# cm108_schematic_2022-07-07.net
KiCad netlist of a schematic drawn in Altium Designer
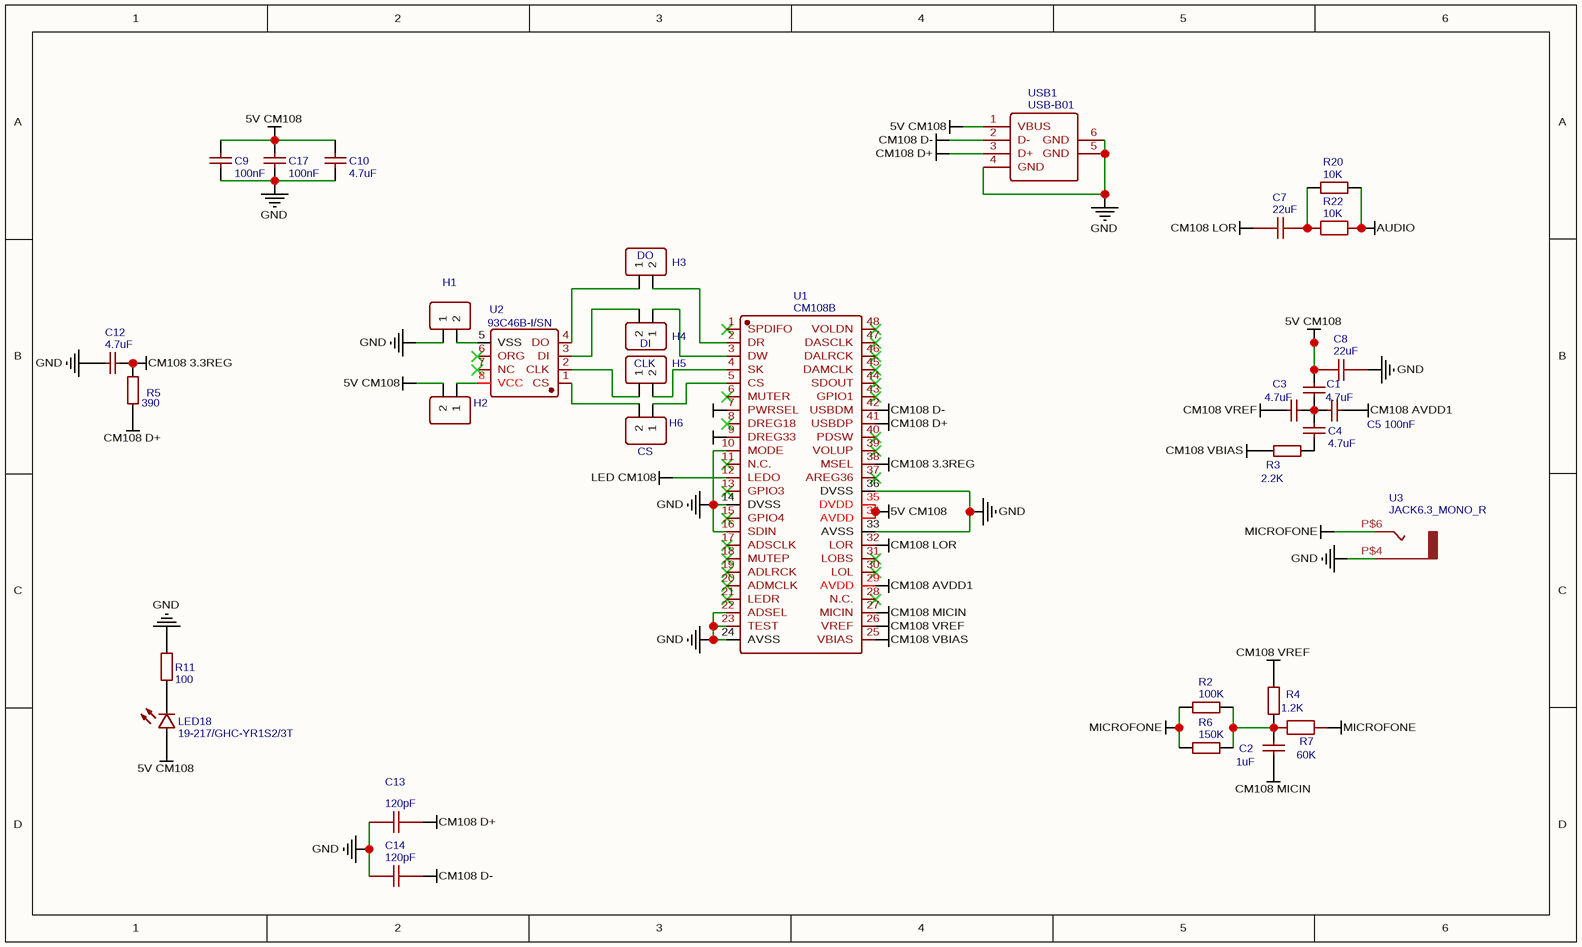
[diagram p0: cm108 schematic_2022-07-07.schdoc]

(export (version "E")
  (design (tool "Eeschema 10.0.6"))
  (components
    (comp (ref "C1")
      (value "4.7uF")
      (fields
        (field (name "BOM_MANUFACTURER PART") "CL21A475KAQNNNE")
        (field (name "BOM_SUPPLIER PART") "C1779")
      )
      (libsource (lib "altium-import") (part "root_3_4.7uF_"))
    )
    (comp (ref "C2")
      (value "1uF")
      (fields
        (field (name "BOM_MANUFACTURER PART") "CL21B105KBFNNNE")
        (field (name "BOM_SUPPLIER PART") "C28323")
      )
      (libsource (lib "altium-import") (part "root_1_1uF_"))
    )
    (comp (ref "C3")
      (value "4.7uF")
      (fields
        (field (name "BOM_MANUFACTURER PART") "CL21A475KAQNNNE")
        (field (name "BOM_SUPPLIER PART") "C1779")
      )
      (libsource (lib "altium-import") (part "root_2_4.7uF_"))
    )
    (comp (ref "C4")
      (value "4.7uF")
      (fields
        (field (name "BOM_MANUFACTURER PART") "CL21A475KAQNNNE")
        (field (name "BOM_SUPPLIER PART") "C1779")
      )
      (libsource (lib "altium-import") (part "root_3_4.7uF_"))
    )
    (comp (ref "C5")
      (value "100nF")
      (fields
        (field (name "BOM_MANUFACTURER PART") "CC0805KRX7R9BB104")
        (field (name "BOM_SUPPLIER PART") "C49678")
      )
      (libsource (lib "altium-import") (part "root_0_100nF_"))
    )
    (comp (ref "C7")
      (value "22uF")
      (fields
        (field (name "BOM_MANUFACTURER PART") "CL21A226MAQNNNE")
        (field (name "BOM_SUPPLIER PART") "C45783")
      )
      (libsource (lib "altium-import") (part "root_0_22uF_"))
    )
    (comp (ref "C8")
      (value "22uF")
      (fields
        (field (name "BOM_MANUFACTURER PART") "CL21A226MAQNNNE")
        (field (name "BOM_SUPPLIER PART") "C45783")
      )
      (libsource (lib "altium-import") (part "root_0_22uF_"))
    )
    (comp (ref "C9")
      (value "100nF")
      (fields
        (field (name "BOM_MANUFACTURER PART") "CC0805KRX7R9BB104")
        (field (name "BOM_SUPPLIER PART") "C49678")
      )
      (libsource (lib "altium-import") (part "root_1_100nF_"))
    )
    (comp (ref "C10")
      (value "4.7uF")
      (fields
        (field (name "BOM_MANUFACTURER PART") "CL21A475KAQNNNE")
        (field (name "BOM_SUPPLIER PART") "C1779")
      )
      (libsource (lib "altium-import") (part "root_1_4.7uF_"))
    )
    (comp (ref "C12")
      (value "4.7uF")
      (fields
        (field (name "BOM_MANUFACTURER PART") "CL21A475KAQNNNE")
        (field (name "BOM_SUPPLIER PART") "C1779")
      )
      (libsource (lib "altium-import") (part "root_0_4.7uF_"))
    )
    (comp (ref "C13")
      (value "120pF")
      (fields
        (field (name "BOM_SUPPLIER PART") "C159770")
        (field (name "BOM_MANUFACTURER PART") "CL21C121JBANNNC")
        (field (name "CONTRIBUTOR") "LCSC")
      )
      (libsource (lib "altium-import") (part "root_1_120pF_"))
    )
    (comp (ref "C14")
      (value "120pF")
      (fields
        (field (name "BOM_SUPPLIER PART") "C159770")
        (field (name "BOM_MANUFACTURER PART") "CL21C121JBANNNC")
        (field (name "CONTRIBUTOR") "LCSC")
      )
      (libsource (lib "altium-import") (part "root_1_120pF_"))
    )
    (comp (ref "C17")
      (value "100nF")
      (fields
        (field (name "BOM_MANUFACTURER PART") "CC0805KRX7R9BB104")
        (field (name "BOM_SUPPLIER PART") "C49678")
      )
      (libsource (lib "altium-import") (part "root_1_100nF_"))
    )
    (comp (ref "H1")
      (value "HDR-F-2.54_1x2")
      (fields (field (name "BOM_SUPPLIER PART") "C49661") (field (name "CONTRIBUTOR") "LCEDA_Lib"))
      (libsource (lib "altium-import") (part "root_1_HDR-F-2.54_1x2_"))
    )
    (comp (ref "H2")
      (value "HDR-F-2.54_1x2")
      (fields (field (name "BOM_SUPPLIER PART") "C49661") (field (name "CONTRIBUTOR") "LCEDA_Lib"))
      (libsource (lib "altium-import") (part "root_3_HDR-F-2.54_1x2_"))
    )
    (comp (ref "H3")
      (value "DO")
      (fields (field (name "BOM_SUPPLIER PART") "C49661") (field (name "CONTRIBUTOR") "LCEDA_Lib"))
      (libsource (lib "altium-import") (part "root_1_DO_"))
    )
    (comp (ref "H4")
      (value "DI")
      (fields (field (name "BOM_SUPPLIER PART") "C49661") (field (name "CONTRIBUTOR") "LCEDA_Lib"))
      (libsource (lib "altium-import") (part "root_3_DI_"))
    )
    (comp (ref "H5")
      (value "CLK")
      (fields (field (name "BOM_SUPPLIER PART") "C49661") (field (name "CONTRIBUTOR") "LCEDA_Lib"))
      (libsource (lib "altium-import") (part "root_1_CLK_"))
    )
    (comp (ref "H6")
      (value "CS")
      (fields (field (name "BOM_SUPPLIER PART") "C49661") (field (name "CONTRIBUTOR") "LCEDA_Lib"))
      (libsource (lib "altium-import") (part "root_3_CS_"))
    )
    (comp (ref "LED18")
      (value "19-217/GHC-YR1S2/3T")
      (fields (field (name "BOM_SUPPLIER PART") "C72043"))
      (libsource (lib "altium-import") (part "root_1_19-217/GHC-YR1S2/3T_"))
    )
    (comp (ref "R2")
      (value "100K")
      (fields
        (field (name "BOM_MANUFACTURER PART") "0603WAF1003T5E")
        (field (name "BOM_SUPPLIER PART") "C25803")
      )
      (libsource (lib "altium-import") (part "root_2_100K_"))
    )
    (comp (ref "R3")
      (value "2.2K")
      (fields
        (field (name "BOM_MANUFACTURER PART") "0805W8F2201T5E")
        (field (name "BOM_SUPPLIER PART") "C17520")
      )
      (libsource (lib "altium-import") (part "root_2_2.2K_"))
    )
    (comp (ref "R4")
      (value "1.2K")
      (fields
        (field (name "BOM_MANUFACTURER PART") "0805W8F1201T5E")
        (field (name "BOM_SUPPLIER PART") "C17379")
      )
      (libsource (lib "altium-import") (part "root_1_1.2K_"))
    )
    (comp (ref "R5")
      (value "390")
      (fields
        (field (name "BOM_MANUFACTURER PART") "1206W4J0391T5E")
        (field (name "BOM_SUPPLIER PART") "C25378")
      )
      (libsource (lib "altium-import") (part "root_1_390_"))
    )
    (comp (ref "R6")
      (value "150K")
      (fields
        (field (name "BOM_MANUFACTURER PART") "0603WAF1503T5E")
        (field (name "BOM_SUPPLIER PART") "C22807")
      )
      (libsource (lib "altium-import") (part "root_2_150K_"))
    )
    (comp (ref "R7")
      (value "60K")
      (fields
        (field (name "BOM_SUPPLIER PART") "C410695")
        (field (name "BOM_MANUFACTURER PART") "RN 1/4W 10K F T/B A1")
        (field (name "CONTRIBUTOR") "LCSC")
      )
      (libsource (lib "altium-import") (part "root_0_60K_"))
    )
    (comp (ref "R11")
      (value "100")
      (fields
        (field (name "BOM_MANUFACTURER PART") "0805W8F1000T5E")
        (field (name "BOM_SUPPLIER PART") "C17408")
      )
      (libsource (lib "altium-import") (part "root_1_100_"))
    )
    (comp (ref "R20")
      (value "10K")
      (fields
        (field (name "BOM_MANUFACTURER PART") "0603WAF1002T5E")
        (field (name "BOM_SUPPLIER PART") "C25804")
      )
      (libsource (lib "altium-import") (part "root_2_10K_"))
    )
    (comp (ref "R22")
      (value "10K")
      (fields
        (field (name "BOM_SUPPLIER PART") "C410695")
        (field (name "BOM_MANUFACTURER PART") "RN 1/4W 10K F T/B A1")
        (field (name "CONTRIBUTOR") "LCSC")
      )
      (libsource (lib "") (part "root_2_10K__1"))
    )
    (comp (ref "U1")
      (value "CM108B")
      (fields (field (name "BOM_SUPPLIER PART") "C371347") (field (name "CONTRIBUTOR") "LCSC"))
      (libsource (lib "altium-import") (part "root_0_CM108B_"))
    )
    (comp (ref "U2")
      (value "93C46B-I/SN")
      (fields (field (name "BOM_SUPPLIER PART") "C615354") (field (name "CONTRIBUTOR") "LCSC"))
      (libsource (lib "altium-import") (part "root_2_93C46B-I/SN_"))
    )
    (comp (ref "U3")
      (value "JACK6.3_MONO_R")
      (libsource (lib "altium-import") (part "root_0_JACK6.3_MONO_R_"))
    )
    (comp (ref "USB1")
      (value "USB-B01")
      (fields (field (name "BOM_SUPPLIER PART") "C498173") (field (name "CONTRIBUTOR") "LCSC"))
      (libsource (lib "altium-import") (part "root_0_USB-B01_"))
    )
  )
  (nets
    (net (code "1") (name "5V CM108") (class "Default")
      (node (ref "C1") (pin "1") (pinfunction "1_1") (pintype "passive"))
      (node (ref "C10") (pin "2") (pinfunction "2_2") (pintype "passive"))
      (node (ref "C17") (pin "2") (pinfunction "2_2") (pintype "passive"))
      (node (ref "C8") (pin "1") (pinfunction "1_1") (pintype "passive"))
      (node (ref "C9") (pin "2") (pinfunction "2_2") (pintype "passive"))
      (node (ref "H2") (pin "2") (pinfunction "2_2") (pintype "passive"))
      (node (ref "LED18") (pin "1") (pinfunction "A_1") (pintype "passive"))
      (node (ref "U1") (pin "34") (pinfunction "AVDD_34") (pintype "passive"))
      (node (ref "U1") (pin "35") (pinfunction "DVDD_35") (pintype "passive"))
      (node (ref "USB1") (pin "1") (pinfunction "VBUS_1") (pintype "passive"))
    )
    (net (code "2") (name "AUDIO") (class "Default")
      (node (ref "R20") (pin "1") (pinfunction "1_1") (pintype "passive"))
      (node (ref "R22") (pin "1") (pinfunction "1_1") (pintype "passive"))
    )
    (net (code "3") (name "CM108 3.3REG") (class "Default")
      (node (ref "C12") (pin "2") (pinfunction "2_2") (pintype "passive"))
      (node (ref "R5") (pin "2") (pinfunction "2_2") (pintype "passive"))
      (node (ref "U1") (pin "38") (pinfunction "MSEL_38") (pintype "passive"))
      (node (ref "U1") (pin "7") (pinfunction "PWRSEL_7") (pintype "passive"))
      (node (ref "U1") (pin "9") (pinfunction "DREG33_9") (pintype "passive"))
    )
    (net (code "4") (name "CM108 AVDD1") (class "Default")
      (node (ref "C5") (pin "2") (pinfunction "2_2") (pintype "passive"))
      (node (ref "U1") (pin "29") (pinfunction "AVDD_29") (pintype "passive"))
    )
    (net (code "5") (name "CM108 D+") (class "Default")
      (node (ref "C13") (pin "1") (pinfunction "1_1") (pintype "passive"))
      (node (ref "R5") (pin "1") (pinfunction "1_1") (pintype "passive"))
      (node (ref "U1") (pin "41") (pinfunction "USBDP_41") (pintype "passive"))
      (node (ref "USB1") (pin "3") (pinfunction "D+_3") (pintype "passive"))
    )
    (net (code "6") (name "CM108 D-") (class "Default")
      (node (ref "C14") (pin "1") (pinfunction "1_1") (pintype "passive"))
      (node (ref "U1") (pin "42") (pinfunction "USBDM_42") (pintype "passive"))
      (node (ref "USB1") (pin "2") (pinfunction "D-_2") (pintype "passive"))
    )
    (net (code "7") (name "CM108 LOR") (class "Default")
      (node (ref "C7") (pin "1") (pinfunction "1_1") (pintype "passive"))
      (node (ref "U1") (pin "32") (pinfunction "LOR_32") (pintype "passive"))
    )
    (net (code "8") (name "CM108 MICIN") (class "Default")
      (node (ref "C2") (pin "1") (pinfunction "1_1") (pintype "passive"))
      (node (ref "U1") (pin "27") (pinfunction "MICIN_27") (pintype "passive"))
    )
    (net (code "9") (name "CM108 VBIAS") (class "Default")
      (node (ref "R3") (pin "2") (pinfunction "2_2") (pintype "passive"))
      (node (ref "U1") (pin "25") (pinfunction "VBIAS_25") (pintype "passive"))
    )
    (net (code "10") (name "CM108 VREF") (class "Default")
      (node (ref "C3") (pin "2") (pinfunction "2_2") (pintype "passive"))
      (node (ref "R4") (pin "2") (pinfunction "2_2") (pintype "passive"))
      (node (ref "U1") (pin "26") (pinfunction "VREF_26") (pintype "passive"))
    )
    (net (code "11") (name "GND") (class "Default")
      (node (ref "C10") (pin "1") (pinfunction "1_1") (pintype "passive"))
      (node (ref "C12") (pin "1") (pinfunction "1_1") (pintype "passive"))
      (node (ref "C13") (pin "2") (pinfunction "2_2") (pintype "passive"))
      (node (ref "C14") (pin "2") (pinfunction "2_2") (pintype "passive"))
      (node (ref "C17") (pin "1") (pinfunction "1_1") (pintype "passive"))
      (node (ref "C8") (pin "2") (pinfunction "2_2") (pintype "passive"))
      (node (ref "C9") (pin "1") (pinfunction "1_1") (pintype "passive"))
      (node (ref "H1") (pin "1") (pinfunction "1_1") (pintype "passive"))
      (node (ref "R11") (pin "2") (pinfunction "2_2") (pintype "passive"))
      (node (ref "U1") (pin "10") (pinfunction "MODE_10") (pintype "passive"))
      (node (ref "U1") (pin "14") (pinfunction "DVSS_14") (pintype "passive"))
      (node (ref "U1") (pin "16") (pinfunction "SDIN_16") (pintype "passive"))
      (node (ref "U1") (pin "22") (pinfunction "ADSEL_22") (pintype "passive"))
      (node (ref "U1") (pin "23") (pinfunction "TEST_23") (pintype "passive"))
      (node (ref "U1") (pin "24") (pinfunction "AVSS_24") (pintype "passive"))
      (node (ref "U1") (pin "33") (pinfunction "AVSS_33") (pintype "passive"))
      (node (ref "U1") (pin "36") (pinfunction "DVSS_36") (pintype "passive"))
      (node (ref "U3") (pin "P$4") (pinfunction "1_P$4") (pintype "passive"))
      (node (ref "USB1") (pin "4") (pinfunction "GND_4") (pintype "passive"))
      (node (ref "USB1") (pin "5") (pinfunction "GND_5") (pintype "passive"))
      (node (ref "USB1") (pin "6") (pinfunction "GND_6") (pintype "passive"))
    )
    (net (code "12") (name "LED CM108") (class "Default")
      (node (ref "U1") (pin "12") (pinfunction "LEDO_12") (pintype "passive"))
    )
    (net (code "13") (name "MICROFONE") (class "Default")
      (node (ref "R2") (pin "2") (pinfunction "2_2") (pintype "passive"))
      (node (ref "R6") (pin "2") (pinfunction "2_2") (pintype "passive"))
      (node (ref "R7") (pin "2") (pinfunction "2_2") (pintype "passive"))
      (node (ref "U3") (pin "P$6") (pinfunction "2_P$6") (pintype "passive"))
    )
    (net (code "14") (name "Net-(C1-Pad2)") (class "Default")
      (node (ref "C1") (pin "2") (pinfunction "2_2") (pintype "passive"))
      (node (ref "C3") (pin "1") (pinfunction "1_1") (pintype "passive"))
      (node (ref "C4") (pin "1") (pinfunction "1_1") (pintype "passive"))
      (node (ref "C5") (pin "1") (pinfunction "1_1") (pintype "passive"))
    )
    (net (code "15") (name "Net-(C2-Pad2)") (class "Default")
      (node (ref "C2") (pin "2") (pinfunction "2_2") (pintype "passive"))
      (node (ref "R2") (pin "1") (pinfunction "1_1") (pintype "passive"))
      (node (ref "R4") (pin "1") (pinfunction "1_1") (pintype "passive"))
      (node (ref "R6") (pin "1") (pinfunction "1_1") (pintype "passive"))
      (node (ref "R7") (pin "1") (pinfunction "1_1") (pintype "passive"))
    )
    (net (code "16") (name "Net-(C4-Pad2)") (class "Default")
      (node (ref "C4") (pin "2") (pinfunction "2_2") (pintype "passive"))
      (node (ref "R3") (pin "1") (pinfunction "1_1") (pintype "passive"))
    )
    (net (code "17") (name "Net-(C7-Pad2)") (class "Default")
      (node (ref "C7") (pin "2") (pinfunction "2_2") (pintype "passive"))
      (node (ref "R20") (pin "2") (pinfunction "2_2") (pintype "passive"))
      (node (ref "R22") (pin "2") (pinfunction "2_2") (pintype "passive"))
    )
    (net (code "18") (name "Net-(LED18-C)") (class "Default")
      (node (ref "LED18") (pin "2") (pinfunction "C_2") (pintype "passive"))
      (node (ref "R11") (pin "1") (pinfunction "1_1") (pintype "passive"))
    )
    (net (code "19") (name "Net-(U1-CS)") (class "Default")
      (node (ref "H6") (pin "1") (pinfunction "1_1") (pintype "passive"))
      (node (ref "U1") (pin "5") (pinfunction "CS_5") (pintype "passive"))
    )
    (net (code "20") (name "Net-(U1-DR)") (class "Default")
      (node (ref "H3") (pin "2") (pinfunction "2_2") (pintype "passive"))
      (node (ref "U1") (pin "2") (pinfunction "DR_2") (pintype "passive"))
    )
    (net (code "21") (name "Net-(U1-DW)") (class "Default")
      (node (ref "H4") (pin "1") (pinfunction "1_1") (pintype "passive"))
      (node (ref "U1") (pin "3") (pinfunction "DW_3") (pintype "passive"))
    )
    (net (code "22") (name "Net-(U1-SK)") (class "Default")
      (node (ref "H5") (pin "2") (pinfunction "2_2") (pintype "passive"))
      (node (ref "U1") (pin "4") (pinfunction "SK_4") (pintype "passive"))
    )
    (net (code "23") (name "Net-(U2-CLK)") (class "Default")
      (node (ref "H5") (pin "1") (pinfunction "1_1") (pintype "passive"))
      (node (ref "U2") (pin "2") (pinfunction "CLK_2") (pintype "passive"))
    )
    (net (code "24") (name "Net-(U2-CS)") (class "Default")
      (node (ref "H6") (pin "2") (pinfunction "2_2") (pintype "passive"))
      (node (ref "U2") (pin "1") (pinfunction "CS_1") (pintype "passive"))
    )
    (net (code "25") (name "Net-(U2-DI)") (class "Default")
      (node (ref "H4") (pin "2") (pinfunction "2_2") (pintype "passive"))
      (node (ref "U2") (pin "3") (pinfunction "DI_3") (pintype "passive"))
    )
    (net (code "26") (name "Net-(U2-DO)") (class "Default")
      (node (ref "H3") (pin "1") (pinfunction "1_1") (pintype "passive"))
      (node (ref "U2") (pin "4") (pinfunction "DO_4") (pintype "passive"))
    )
    (net (code "27") (name "Net-(U2-VCC)") (class "Default")
      (node (ref "H2") (pin "1") (pinfunction "1_1") (pintype "passive"))
      (node (ref "U2") (pin "8") (pinfunction "VCC_8") (pintype "passive"))
    )
    (net (code "28") (name "Net-(U2-VSS)") (class "Default")
      (node (ref "H1") (pin "2") (pinfunction "2_2") (pintype "passive"))
      (node (ref "U2") (pin "5") (pinfunction "VSS_5") (pintype "passive"))
    )
    (net (code "29") (name "unconnected-(U1-ADLRCK-Pad19)") (class "Default")
      (node (ref "U1") (pin "19") (pinfunction "ADLRCK_19") (pintype "passive+no_connect"))
    )
    (net (code "30") (name "unconnected-(U1-ADMCLK-Pad20)") (class "Default")
      (node (ref "U1") (pin "20") (pinfunction "ADMCLK_20") (pintype "passive+no_connect"))
    )
    (net (code "31") (name "unconnected-(U1-ADSCLK-Pad17)") (class "Default")
      (node (ref "U1") (pin "17") (pinfunction "ADSCLK_17") (pintype "passive+no_connect"))
    )
    (net (code "32") (name "unconnected-(U1-AREG36-Pad37)") (class "Default")
      (node (ref "U1") (pin "37") (pinfunction "AREG36_37") (pintype "passive+no_connect"))
    )
    (net (code "33") (name "unconnected-(U1-DALRCK-Pad46)") (class "Default")
      (node (ref "U1") (pin "46") (pinfunction "DALRCK_46") (pintype "passive+no_connect"))
    )
    (net (code "34") (name "unconnected-(U1-DAMCLK-Pad45)") (class "Default")
      (node (ref "U1") (pin "45") (pinfunction "DAMCLK_45") (pintype "passive+no_connect"))
    )
    (net (code "35") (name "unconnected-(U1-DASCLK-Pad47)") (class "Default")
      (node (ref "U1") (pin "47") (pinfunction "DASCLK_47") (pintype "passive+no_connect"))
    )
    (net (code "36") (name "unconnected-(U1-DREG18-Pad8)") (class "Default")
      (node (ref "U1") (pin "8") (pinfunction "DREG18_8") (pintype "passive+no_connect"))
    )
    (net (code "37") (name "unconnected-(U1-GPIO1-Pad43)") (class "Default")
      (node (ref "U1") (pin "43") (pinfunction "GPIO1_43") (pintype "passive+no_connect"))
    )
    (net (code "38") (name "unconnected-(U1-GPIO3-Pad13)") (class "Default")
      (node (ref "U1") (pin "13") (pinfunction "GPIO3_13") (pintype "passive+no_connect"))
    )
    (net (code "39") (name "unconnected-(U1-GPIO4-Pad15)") (class "Default")
      (node (ref "U1") (pin "15") (pinfunction "GPIO4_15") (pintype "passive+no_connect"))
    )
    (net (code "40") (name "unconnected-(U1-LEDR-Pad21)") (class "Default")
      (node (ref "U1") (pin "21") (pinfunction "LEDR_21") (pintype "passive+no_connect"))
    )
    (net (code "41") (name "unconnected-(U1-LOBS-Pad31)") (class "Default")
      (node (ref "U1") (pin "31") (pinfunction "LOBS_31") (pintype "passive+no_connect"))
    )
    (net (code "42") (name "unconnected-(U1-LOL-Pad30)") (class "Default")
      (node (ref "U1") (pin "30") (pinfunction "LOL_30") (pintype "passive+no_connect"))
    )
    (net (code "43") (name "unconnected-(U1-MUTEP-Pad18)") (class "Default")
      (node (ref "U1") (pin "18") (pinfunction "MUTEP_18") (pintype "passive+no_connect"))
    )
    (net (code "44") (name "unconnected-(U1-MUTER-Pad6)") (class "Default")
      (node (ref "U1") (pin "6") (pinfunction "MUTER_6") (pintype "passive+no_connect"))
    )
    (net (code "45") (name "unconnected-(U1-N.C.-Pad11)") (class "Default")
      (node (ref "U1") (pin "11") (pinfunction "N.C._11") (pintype "passive+no_connect"))
    )
    (net (code "46") (name "unconnected-(U1-N.C.-Pad28)") (class "Default")
      (node (ref "U1") (pin "28") (pinfunction "N.C._28") (pintype "passive+no_connect"))
    )
    (net (code "47") (name "unconnected-(U1-PDSW-Pad40)") (class "Default")
      (node (ref "U1") (pin "40") (pinfunction "PDSW_40") (pintype "passive+no_connect"))
    )
    (net (code "48") (name "unconnected-(U1-SDOUT-Pad44)") (class "Default")
      (node (ref "U1") (pin "44") (pinfunction "SDOUT_44") (pintype "passive+no_connect"))
    )
    (net (code "49") (name "unconnected-(U1-SPDIFO-Pad1)") (class "Default")
      (node (ref "U1") (pin "1") (pinfunction "SPDIFO_1") (pintype "passive+no_connect"))
    )
    (net (code "50") (name "unconnected-(U1-VOLDN-Pad48)") (class "Default")
      (node (ref "U1") (pin "48") (pinfunction "VOLDN_48") (pintype "passive+no_connect"))
    )
    (net (code "51") (name "unconnected-(U1-VOLUP-Pad39)") (class "Default")
      (node (ref "U1") (pin "39") (pinfunction "VOLUP_39") (pintype "passive+no_connect"))
    )
    (net (code "52") (name "unconnected-(U2-NC-Pad7)") (class "Default")
      (node (ref "U2") (pin "7") (pinfunction "NC_7") (pintype "passive+no_connect"))
    )
    (net (code "53") (name "unconnected-(U2-ORG-Pad6)") (class "Default")
      (node (ref "U2") (pin "6") (pinfunction "ORG_6") (pintype "passive+no_connect"))
    )
  )
)
